# 110_ESP32s3.net
KiCad netlist of a schematic drawn in Altium Designer
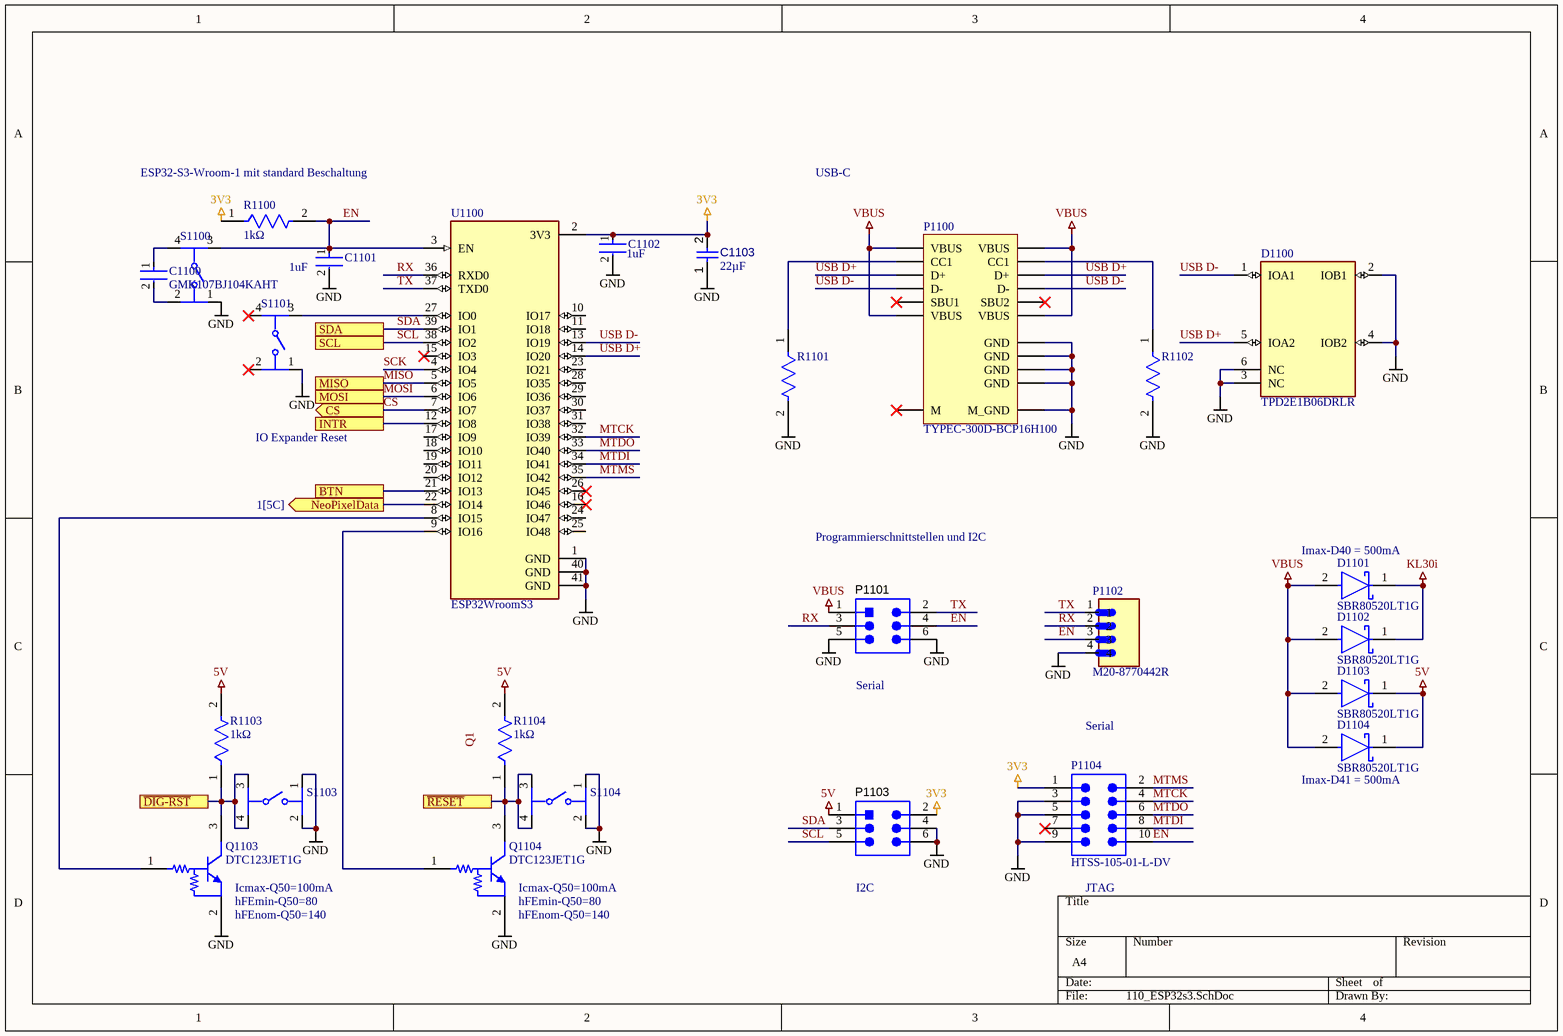
[diagram p0: 110_ESP32s3.SchDoc]

(export (version "E")
  (design (tool "Eeschema 10.0.6"))
  (components
    (comp (ref "C1100")
      (value "GMK107BJ104KAHT")
      (footprint "FP-0603-L_1_6_0_1-W_0_8_0-IPC_B")
      (description "Ceramic Capacitor Automotive 0.1uF ±10% 35V X5R 0603")
      (fields (field (name "TOLERANCE") "10%"))
      (libsource (lib "Altium Content Vault") (part "02cd4be3c70576c341d710602a673aa"))
    )
    (comp (ref "C1101")
      (value "1uF")
      (footprint "FP-CGA3E-0_3-0_1-MFG")
      (description "Cap Ceramic 1uF 35V X7R 10% Pad SMD 0603 +125°C Automotive T/R\r\nCGA3E1X7R1V105K080AC")
      (fields (field (name "TOLERANCE") "10%"))
      (libsource (lib "Altium Content Vault") (part "b4654b650e69147ec39a6b967a45e02"))
    )
    (comp (ref "C1102")
      (value "1uF")
      (footprint "FP-CGA3E-0_3-0_1-MFG")
      (description "Cap Ceramic 1uF 35V X7R 10% Pad SMD 0603 +125°C Automotive T/R\r\nCGA3E1X7R1V105K080AC")
      (fields (field (name "TOLERANCE") "10%"))
      (libsource (lib "Altium Content Vault") (part "b4654b650e69147ec39a6b967a45e02"))
    )
    (comp (ref "C1103")
      (value "22µF")
      (footprint "CAPC0805(2012)145_L")
      (description "Chip Capacitor, 22µF +/-40%, 16V, 0805, Thickness 1.45 mm")
      (fields (field (name "TOLERANCE") "5%") (field (name "Comment") "Capacitor 22µF +/-40% 16V 0805"))
      (libsource (lib "Milutin") (part "CAP-NP-2"))
    )
    (comp (ref "D1100")
      (value "TPD2E1B06DRLR")
      (footprint "FP-DRL0006A-MFG")
      (description "TVS DIODE 5.5V 15V 6SOT")
      (fields
        (field (name "OCTOPART") "https://octopart.com/tpd2e1b06drlr-texas+instruments-30488860")
        (field (name "MANUFACTURER") "Texas Instruments")
      )
      (libsource (lib "Altium Content Vault") (part "f3dc085ebb28d99bc65c213f373c040"))
    )
    (comp (ref "D1101")
      (value "SBR80520LT1G")
      (footprint "FP-425-04-MFG")
      (description "DIODE SCHOTTKY 20V 500MA SOD123")
      (libsource (lib "Altium Content Vault") (part "1d6ec82d83fb6aee721767c19dac4b9"))
    )
    (comp (ref "D1102")
      (value "SBR80520LT1G")
      (footprint "FP-425-04-MFG")
      (description "DIODE SCHOTTKY 20V 500MA SOD123")
      (libsource (lib "Altium Content Vault") (part "1d6ec82d83fb6aee721767c19dac4b9"))
    )
    (comp (ref "D1103")
      (value "SBR80520LT1G")
      (footprint "FP-425-04-MFG")
      (description "DIODE SCHOTTKY 20V 500MA SOD123")
      (libsource (lib "Altium Content Vault") (part "1d6ec82d83fb6aee721767c19dac4b9"))
    )
    (comp (ref "D1104")
      (value "SBR80520LT1G")
      (footprint "FP-425-04-MFG")
      (description "DIODE SCHOTTKY 20V 500MA SOD123")
      (libsource (lib "Altium Content Vault") (part "1d6ec82d83fb6aee721767c19dac4b9"))
    )
    (comp (ref "P1100")
      (value "TYPEC-300D-BCP16H100")
      (footprint "TYPEC-300D-BCP16H100-Footprint-1")
      (description "Vertical USB Type C Connector")
      (libsource (lib "Milutin") (part "TYPEC-300D-BCP16H100-Symbol-1"))
    )
    (comp (ref "P1101")
      (value "5-146130-2")
      (footprint "TECO-5-146130-2_V")
      (description "Male Header, Pitch 2.54 mm, 2 x 3 Position, Height 8.13 mm, -65 to 125 degC, RoHS, Tube")
      (libsource (lib "Altium Content Vault") (part "CN-2P-M-R6"))
    )
    (comp (ref "P1102")
      (value "M20-8770442R")
      (footprint "HARWIN_M20-8770442R")
      (description "Connector Header Surface Mount 4 position 0.100 (2.54mm)")
      (fields (field (name "MF") "Harwin Inc."))
      (libsource (lib "AltiumLib_MILUTIN") (part "M20-8770442R"))
    )
    (comp (ref "P1103")
      (value "5-146130-2")
      (footprint "TECO-5-146130-2_V")
      (description "Male Header, Pitch 2.54 mm, 2 x 3 Position, Height 8.13 mm, -65 to 125 degC, RoHS, Tube")
      (libsource (lib "Altium Content Vault") (part "CN-2P-M-R6"))
    )
    (comp (ref "P1104")
      (value "HTSS-105-01-L-DV")
      (footprint "SMTC-HTSS-105-01-X-DV")
      (fields (field (name "MANUFACTURER") "Samtec"))
      (libsource (lib "Altium Content Vault") (part "SMTC-HTSS-105-01-X-DV"))
    )
    (comp (ref "Q1103")
      (value "DTC123JET1G")
      (footprint "ONSC-SC-75-3-463-01_V")
      (fields (field (name "MANUFACTURER") "On Semiconductor"))
      (libsource (lib "Altium Content Vault") (part "ONSC-BRT-NPN-B1E2C3-3"))
    )
    (comp (ref "Q1104")
      (value "DTC123JET1G")
      (footprint "ONSC-SC-75-3-463-01_V")
      (fields (field (name "MANUFACTURER") "On Semiconductor"))
      (libsource (lib "Altium Content Vault") (part "ONSC-BRT-NPN-B1E2C3-3"))
    )
    (comp (ref "R1100")
      (value "1kΩ")
      (footprint "FP-CRCW0603-e3-MFG")
      (description "RES Thick Film, 1kΩ, 1%, 0.1W, 100ppm/°C, 0603, CRCW06031K00FKEA")
      (fields (field (name "TOLERANCE") "1%"))
      (libsource (lib "Altium Content Vault") (part "1029c3af85768c4190bb7ad29bc67b5"))
    )
    (comp (ref "R1101")
      (value "CRCW06035K10FKEA")
      (footprint "FP-CRCW0603-e3-IPC_C")
      (description "RES Thick Film, 5.1kΩ, 1%, 0.1W, 100ppm/°C, 0603")
      (fields (field (name "TOLERANCE") "1%"))
      (libsource (lib "Altium Content Vault") (part "1029c3af85768c4190bb7ad29bc67b5"))
    )
    (comp (ref "R1102")
      (value "CRCW06035K10FKEA")
      (footprint "FP-CRCW0603-e3-IPC_C")
      (description "RES Thick Film, 5.1kΩ, 1%, 0.1W, 100ppm/°C, 0603")
      (fields (field (name "TOLERANCE") "1%"))
      (libsource (lib "Altium Content Vault") (part "1029c3af85768c4190bb7ad29bc67b5"))
    )
    (comp (ref "R1103")
      (value "1kΩ")
      (footprint "FP-CRCW0603-e3-MFG")
      (description "RES Thick Film, 1kΩ, 1%, 0.1W, 100ppm/°C, 0603, CRCW06031K00FKEA")
      (fields (field (name "TOLERANCE") "1%"))
      (libsource (lib "Altium Content Vault") (part "1029c3af85768c4190bb7ad29bc67b5"))
    )
    (comp (ref "R1104")
      (value "1kΩ")
      (footprint "FP-CRCW0603-e3-MFG")
      (description "RES Thick Film, 1kΩ, 1%, 0.1W, 100ppm/°C, 0603, CRCW06031K00FKEA")
      (fields (field (name "TOLERANCE") "1%"))
      (libsource (lib "Altium Content Vault") (part "1029c3af85768c4190bb7ad29bc67b5"))
    )
    (comp (ref "S1100")
      (value "~")
      (footprint "FP-PTS645SM43SMTR92LFS-MFG")
      (description "SWITCH TACTILE SPST-NO 0.05A 12V\r\nPTS645SM43SMTR92LFS")
      (libsource (lib "Altium Content Vault") (part "1adf0dd01260c80cf25a44bfd6b99ba"))
    )
    (comp (ref "S1101")
      (value "~")
      (footprint "FP-PTS645SM43SMTR92LFS-MFG")
      (description "SWITCH TACTILE SPST-NO 0.05A 12V\r\nPTS645SM43SMTR92LFS")
      (libsource (lib "Altium Content Vault") (part "1adf0dd01260c80cf25a44bfd6b99ba"))
    )
    (comp (ref "S1103")
      (value "~")
      (footprint "FP-PTS645SM43SMTR92LFS-MFG")
      (description "SWITCH TACTILE SPST-NO 0.05A 12V\r\nPTS645SM43SMTR92LFS")
      (libsource (lib "Altium Content Vault") (part "1adf0dd01260c80cf25a44bfd6b99ba"))
    )
    (comp (ref "S1104")
      (value "~")
      (footprint "FP-PTS645SM43SMTR92LFS-MFG")
      (description "SWITCH TACTILE SPST-NO 0.05A 12V\r\nPTS645SM43SMTR92LFS")
      (libsource (lib "Altium Content Vault") (part "1adf0dd01260c80cf25a44bfd6b99ba"))
    )
    (comp (ref "U1100")
      (value "ESP32WroomS3")
      (footprint "ESP32WroomS3")
      (fields (field (name "SOURCE") "Schaltdose.SchLib"))
      (libsource (lib "Milutin") (part "ESP32WroomS3"))
    )
  )
  (nets
    (net (code "1") (name "/BTN") (class "Default")
      (node (ref "U1100") (pin "21") (pinfunction "IO13_21") (pintype "bidirectional"))
    )
    (net (code "2") (name "/CS") (class "Default")
      (node (ref "U1100") (pin "7") (pinfunction "IO7_7") (pintype "bidirectional"))
    )
    (net (code "3") (name "/EN") (class "Default")
      (node (ref "C1101") (pin "1") (pinfunction "1_1") (pintype "passive"))
      (node (ref "P1101") (pin "4") (pinfunction "4_4") (pintype "passive"))
      (node (ref "P1102") (pin "3") (pinfunction "3_3") (pintype "passive"))
      (node (ref "P1104") (pin "10") (pinfunction "10_10") (pintype "passive"))
      (node (ref "R1100") (pin "2") (pinfunction "2_2") (pintype "passive"))
      (node (ref "S1100") (pin "3") (pinfunction "3_3") (pintype "passive"))
      (node (ref "U1100") (pin "3") (pinfunction "EN_3") (pintype "input"))
    )
    (net (code "4") (name "/INTR") (class "Default")
      (node (ref "U1100") (pin "12") (pinfunction "IO8_12") (pintype "bidirectional"))
    )
    (net (code "5") (name "/MISO") (class "Default")
      (node (ref "U1100") (pin "5") (pinfunction "IO5_5") (pintype "bidirectional"))
    )
    (net (code "6") (name "/MOSI") (class "Default")
      (node (ref "U1100") (pin "6") (pinfunction "IO6_6") (pintype "bidirectional"))
    )
    (net (code "7") (name "/MTCK") (class "Default")
      (node (ref "P1104") (pin "4") (pinfunction "4_4") (pintype "passive"))
      (node (ref "U1100") (pin "32") (pinfunction "IO39_32") (pintype "bidirectional"))
    )
    (net (code "8") (name "/MTDI") (class "Default")
      (node (ref "P1104") (pin "8") (pinfunction "8_8") (pintype "passive"))
      (node (ref "U1100") (pin "34") (pinfunction "IO41_34") (pintype "bidirectional"))
    )
    (net (code "9") (name "/MTDO") (class "Default")
      (node (ref "P1104") (pin "6") (pinfunction "6_6") (pintype "passive"))
      (node (ref "U1100") (pin "33") (pinfunction "IO40_33") (pintype "bidirectional"))
    )
    (net (code "10") (name "/MTMS") (class "Default")
      (node (ref "P1104") (pin "2") (pinfunction "2_2") (pintype "passive"))
      (node (ref "U1100") (pin "35") (pinfunction "IO42_35") (pintype "bidirectional"))
    )
    (net (code "11") (name "/NeoPixelData") (class "Default")
      (node (ref "U1100") (pin "22") (pinfunction "IO14_22") (pintype "bidirectional"))
    )
    (net (code "13") (name "/RX") (class "Default")
      (node (ref "P1101") (pin "3") (pinfunction "3_3") (pintype "passive"))
      (node (ref "P1102") (pin "2") (pinfunction "2_2") (pintype "passive"))
      (node (ref "U1100") (pin "36") (pinfunction "RXD0_36") (pintype "bidirectional"))
    )
    (net (code "14") (name "/SCK") (class "Default")
      (node (ref "U1100") (pin "4") (pinfunction "IO4_4") (pintype "bidirectional"))
    )
    (net (code "15") (name "/SCL") (class "Default")
      (node (ref "P1103") (pin "5") (pinfunction "5_5") (pintype "passive"))
      (node (ref "U1100") (pin "38") (pinfunction "IO2_38") (pintype "bidirectional"))
    )
    (net (code "16") (name "/SDA") (class "Default")
      (node (ref "P1103") (pin "3") (pinfunction "3_3") (pintype "passive"))
      (node (ref "U1100") (pin "39") (pinfunction "IO1_39") (pintype "bidirectional"))
    )
    (net (code "17") (name "/TX") (class "Default")
      (node (ref "P1101") (pin "2") (pinfunction "2_2") (pintype "passive"))
      (node (ref "P1102") (pin "1") (pinfunction "1_1") (pintype "passive"))
      (node (ref "U1100") (pin "37") (pinfunction "TXD0_37") (pintype "bidirectional"))
    )
    (net (code "18") (name "/USB D+") (class "Default")
      (node (ref "D1100") (pin "5") (pinfunction "IOA2_5") (pintype "bidirectional"))
      (node (ref "P1100") (pin "A6") (pinfunction "D+_A6") (pintype "passive"))
      (node (ref "P1100") (pin "B6") (pinfunction "D+_B6") (pintype "passive"))
      (node (ref "U1100") (pin "14") (pinfunction "IO20_14") (pintype "bidirectional"))
    )
    (net (code "19") (name "/USB D-") (class "Default")
      (node (ref "D1100") (pin "1") (pinfunction "IOA1_1") (pintype "bidirectional"))
      (node (ref "P1100") (pin "A7") (pinfunction "D-_A7") (pintype "passive"))
      (node (ref "P1100") (pin "B7") (pinfunction "D-_B7") (pintype "passive"))
      (node (ref "U1100") (pin "13") (pinfunction "IO19_13") (pintype "bidirectional"))
    )
    (net (code "20") (name "/~{DIG-RST}") (class "Default")
      (node (ref "Q1103") (pin "3") (pinfunction "C_3") (pintype "passive"))
      (node (ref "R1103") (pin "1") (pinfunction "1_1") (pintype "passive"))
      (node (ref "S1103") (pin "3") (pinfunction "3_3") (pintype "passive"))
      (node (ref "S1103") (pin "4") (pinfunction "4_4") (pintype "passive"))
    )
    (net (code "21") (name "/~{RESET}") (class "Default")
      (node (ref "Q1104") (pin "3") (pinfunction "C_3") (pintype "passive"))
      (node (ref "R1104") (pin "1") (pinfunction "1_1") (pintype "passive"))
      (node (ref "S1104") (pin "3") (pinfunction "3_3") (pintype "passive"))
      (node (ref "S1104") (pin "4") (pinfunction "4_4") (pintype "passive"))
    )
    (net (code "22") (name "3V3") (class "Default")
      (node (ref "C1102") (pin "1") (pinfunction "1_1") (pintype "passive"))
      (node (ref "C1103") (pin "2") (pinfunction "2_2") (pintype "passive"))
      (node (ref "P1103") (pin "2") (pinfunction "2_2") (pintype "passive"))
      (node (ref "P1104") (pin "1") (pinfunction "1_1") (pintype "passive"))
      (node (ref "R1100") (pin "1") (pinfunction "1_1") (pintype "passive"))
      (node (ref "U1100") (pin "2") (pinfunction "3V3_2") (pintype "power_in"))
    )
    (net (code "23") (name "5V") (class "Default")
      (node (ref "D1103") (pin "1") (pinfunction "C_1") (pintype "passive"))
      (node (ref "D1104") (pin "1") (pinfunction "C_1") (pintype "passive"))
      (node (ref "P1103") (pin "1") (pinfunction "1_1") (pintype "passive"))
      (node (ref "R1103") (pin "2") (pinfunction "2_2") (pintype "passive"))
      (node (ref "R1104") (pin "2") (pinfunction "2_2") (pintype "passive"))
    )
    (net (code "24") (name "GND") (class "Default")
      (node (ref "C1101") (pin "2") (pinfunction "2_2") (pintype "passive"))
      (node (ref "C1102") (pin "2") (pinfunction "2_2") (pintype "passive"))
      (node (ref "C1103") (pin "1") (pinfunction "1_1") (pintype "passive"))
      (node (ref "D1100") (pin "2") (pinfunction "IOB1_2") (pintype "bidirectional"))
      (node (ref "D1100") (pin "3") (pinfunction "NC_3") (pintype "passive"))
      (node (ref "D1100") (pin "4") (pinfunction "IOB2_4") (pintype "bidirectional"))
      (node (ref "D1100") (pin "6") (pinfunction "NC_6") (pintype "passive"))
      (node (ref "P1100") (pin "A1") (pinfunction "GND_A1") (pintype "passive"))
      (node (ref "P1100") (pin "A12") (pinfunction "GND_A12") (pintype "passive"))
      (node (ref "P1100") (pin "B1") (pinfunction "GND_B1") (pintype "passive"))
      (node (ref "P1100") (pin "B12") (pinfunction "GND_B12") (pintype "passive"))
      (node (ref "P1100") (pin "M_GND") (pinfunction "M_GND_M_GND") (pintype "passive"))
      (node (ref "P1101") (pin "5") (pinfunction "5_5") (pintype "passive"))
      (node (ref "P1101") (pin "6") (pinfunction "6_6") (pintype "passive"))
      (node (ref "P1102") (pin "4") (pinfunction "4_4") (pintype "passive"))
      (node (ref "P1103") (pin "4") (pinfunction "4_4") (pintype "passive"))
      (node (ref "P1103") (pin "6") (pinfunction "6_6") (pintype "passive"))
      (node (ref "P1104") (pin "3") (pinfunction "3_3") (pintype "passive"))
      (node (ref "P1104") (pin "5") (pinfunction "5_5") (pintype "passive"))
      (node (ref "P1104") (pin "9") (pinfunction "9_9") (pintype "passive"))
      (node (ref "Q1103") (pin "2") (pinfunction "E_2") (pintype "passive"))
      (node (ref "Q1104") (pin "2") (pinfunction "E_2") (pintype "passive"))
      (node (ref "R1101") (pin "2") (pinfunction "2_2") (pintype "passive"))
      (node (ref "R1102") (pin "2") (pinfunction "2_2") (pintype "passive"))
      (node (ref "S1100") (pin "1") (pinfunction "1_1") (pintype "passive"))
      (node (ref "S1101") (pin "1") (pinfunction "1_1") (pintype "passive"))
      (node (ref "S1103") (pin "1") (pinfunction "1_1") (pintype "passive"))
      (node (ref "S1103") (pin "2") (pinfunction "2_2") (pintype "passive"))
      (node (ref "S1104") (pin "1") (pinfunction "1_1") (pintype "passive"))
      (node (ref "S1104") (pin "2") (pinfunction "2_2") (pintype "passive"))
      (node (ref "U1100") (pin "1") (pinfunction "GND_1") (pintype "power_in"))
      (node (ref "U1100") (pin "40") (pinfunction "GND_40") (pintype "power_in"))
      (node (ref "U1100") (pin "41") (pinfunction "GND_41") (pintype "power_in"))
    )
    (net (code "25") (name "KL30i") (class "Default")
      (node (ref "D1101") (pin "1") (pinfunction "C_1") (pintype "passive"))
      (node (ref "D1102") (pin "1") (pinfunction "C_1") (pintype "passive"))
    )
    (net (code "26") (name "Net-(C1100-Pad1)") (class "Default")
      (node (ref "C1100") (pin "1") (pinfunction "1_1") (pintype "passive"))
      (node (ref "S1100") (pin "4") (pinfunction "4_4") (pintype "passive"))
    )
    (net (code "27") (name "Net-(C1100-Pad2)") (class "Default")
      (node (ref "C1100") (pin "2") (pinfunction "2_2") (pintype "passive"))
      (node (ref "S1100") (pin "2") (pinfunction "2_2") (pintype "passive"))
    )
    (net (code "28") (name "Net-(P1100-CC1-PadA5)") (class "Default")
      (node (ref "P1100") (pin "A5") (pinfunction "CC1_A5") (pintype "passive"))
      (node (ref "R1101") (pin "1") (pinfunction "1_1") (pintype "passive"))
    )
    (net (code "29") (name "Net-(P1100-CC1-PadB5)") (class "Default")
      (node (ref "P1100") (pin "B5") (pinfunction "CC1_B5") (pintype "passive"))
      (node (ref "R1102") (pin "1") (pinfunction "1_1") (pintype "passive"))
    )
    (net (code "30") (name "Net-(Q1103-B)") (class "Default")
      (node (ref "Q1103") (pin "1") (pinfunction "B_1") (pintype "passive"))
      (node (ref "U1100") (pin "8") (pinfunction "IO15_8") (pintype "bidirectional"))
    )
    (net (code "31") (name "Net-(Q1104-B)") (class "Default")
      (node (ref "Q1104") (pin "1") (pinfunction "B_1") (pintype "passive"))
      (node (ref "U1100") (pin "9") (pinfunction "IO16_9") (pintype "bidirectional"))
    )
    (net (code "32") (name "Net-(U1100-IO0)") (class "Default")
      (node (ref "S1101") (pin "3") (pinfunction "3_3") (pintype "passive"))
      (node (ref "U1100") (pin "27") (pinfunction "IO0_27") (pintype "bidirectional"))
    )
    (net (code "33") (name "VBUS") (class "Default")
      (node (ref "D1101") (pin "2") (pinfunction "A_2") (pintype "passive"))
      (node (ref "D1102") (pin "2") (pinfunction "A_2") (pintype "passive"))
      (node (ref "D1103") (pin "2") (pinfunction "A_2") (pintype "passive"))
      (node (ref "D1104") (pin "2") (pinfunction "A_2") (pintype "passive"))
      (node (ref "P1100") (pin "A4") (pinfunction "VBUS_A4") (pintype "passive"))
      (node (ref "P1100") (pin "A9") (pinfunction "VBUS_A9") (pintype "passive"))
      (node (ref "P1100") (pin "B4") (pinfunction "VBUS_B4") (pintype "passive"))
      (node (ref "P1100") (pin "B9") (pinfunction "VBUS_B9") (pintype "passive"))
      (node (ref "P1101") (pin "1") (pinfunction "1_1") (pintype "passive"))
    )
    (net (code "34") (name "unconnected-(P1100-PadM)") (class "Default")
      (node (ref "P1100") (pin "M") (pinfunction "M_M") (pintype "passive+no_connect"))
    )
    (net (code "35") (name "unconnected-(P1100-SBU1-PadA8)") (class "Default")
      (node (ref "P1100") (pin "A8") (pinfunction "SBU1_A8") (pintype "passive+no_connect"))
    )
    (net (code "36") (name "unconnected-(P1100-SBU2-PadB8)") (class "Default")
      (node (ref "P1100") (pin "B8") (pinfunction "SBU2_B8") (pintype "passive+no_connect"))
    )
    (net (code "37") (name "unconnected-(P1104-Pad7)") (class "Default")
      (node (ref "P1104") (pin "7") (pinfunction "7_7") (pintype "passive+no_connect"))
    )
    (net (code "38") (name "unconnected-(S1101-Pad2)") (class "Default")
      (node (ref "S1101") (pin "2") (pinfunction "2_2") (pintype "passive+no_connect"))
    )
    (net (code "39") (name "unconnected-(S1101-Pad4)") (class "Default")
      (node (ref "S1101") (pin "4") (pinfunction "4_4") (pintype "passive+no_connect"))
    )
    (net (code "40") (name "unconnected-(U1100-IO3-Pad15)") (class "Default")
      (node (ref "U1100") (pin "15") (pinfunction "IO3_15") (pintype "bidirectional+no_connect"))
    )
    (net (code "41") (name "unconnected-(U1100-IO9-Pad17)") (class "Default")
      (node (ref "U1100") (pin "17") (pinfunction "IO9_17") (pintype "bidirectional"))
    )
    (net (code "42") (name "unconnected-(U1100-IO10-Pad18)") (class "Default")
      (node (ref "U1100") (pin "18") (pinfunction "IO10_18") (pintype "bidirectional"))
    )
    (net (code "43") (name "unconnected-(U1100-IO11-Pad19)") (class "Default")
      (node (ref "U1100") (pin "19") (pinfunction "IO11_19") (pintype "bidirectional"))
    )
    (net (code "44") (name "unconnected-(U1100-IO12-Pad20)") (class "Default")
      (node (ref "U1100") (pin "20") (pinfunction "IO12_20") (pintype "bidirectional"))
    )
    (net (code "45") (name "unconnected-(U1100-IO17-Pad10)") (class "Default")
      (node (ref "U1100") (pin "10") (pinfunction "IO17_10") (pintype "bidirectional"))
    )
    (net (code "46") (name "unconnected-(U1100-IO18-Pad11)") (class "Default")
      (node (ref "U1100") (pin "11") (pinfunction "IO18_11") (pintype "bidirectional"))
    )
    (net (code "47") (name "unconnected-(U1100-IO21-Pad23)") (class "Default")
      (node (ref "U1100") (pin "23") (pinfunction "IO21_23") (pintype "bidirectional"))
    )
    (net (code "48") (name "unconnected-(U1100-IO35-Pad28)") (class "Default")
      (node (ref "U1100") (pin "28") (pinfunction "IO35_28") (pintype "bidirectional"))
    )
    (net (code "49") (name "unconnected-(U1100-IO36-Pad29)") (class "Default")
      (node (ref "U1100") (pin "29") (pinfunction "IO36_29") (pintype "bidirectional"))
    )
    (net (code "50") (name "unconnected-(U1100-IO37-Pad30)") (class "Default")
      (node (ref "U1100") (pin "30") (pinfunction "IO37_30") (pintype "bidirectional"))
    )
    (net (code "51") (name "unconnected-(U1100-IO38-Pad31)") (class "Default")
      (node (ref "U1100") (pin "31") (pinfunction "IO38_31") (pintype "bidirectional"))
    )
    (net (code "52") (name "unconnected-(U1100-IO45-Pad26)") (class "Default")
      (node (ref "U1100") (pin "26") (pinfunction "IO45_26") (pintype "bidirectional+no_connect"))
    )
    (net (code "53") (name "unconnected-(U1100-IO46-Pad16)") (class "Default")
      (node (ref "U1100") (pin "16") (pinfunction "IO46_16") (pintype "bidirectional+no_connect"))
    )
    (net (code "54") (name "unconnected-(U1100-IO47-Pad24)") (class "Default")
      (node (ref "U1100") (pin "24") (pinfunction "IO47_24") (pintype "bidirectional"))
    )
    (net (code "55") (name "unconnected-(U1100-IO48-Pad25)") (class "Default")
      (node (ref "U1100") (pin "25") (pinfunction "IO48_25") (pintype "bidirectional"))
    )
  )
)
